# Schematic_diagram.net
KiCad netlist of a schematic drawn in Altium Designer
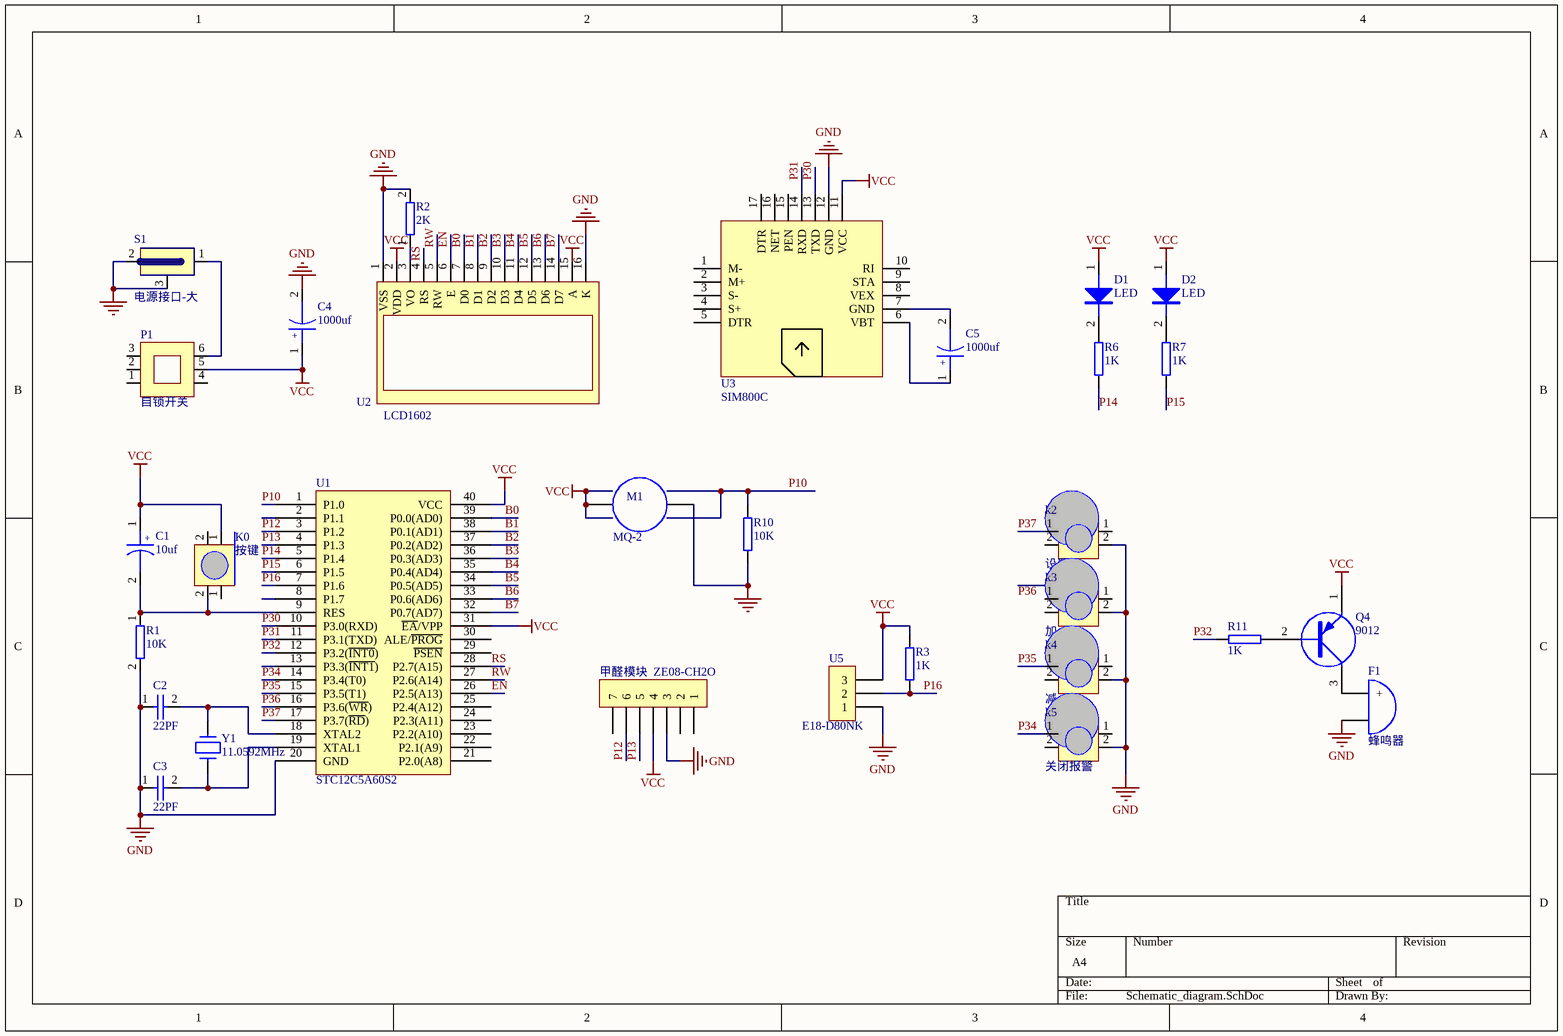
[diagram p0: Schematic_diagram.SchDoc]

(export (version "E")
  (design (tool "Eeschema 10.0.6"))
  (components
    (comp (ref "C1") (value "10uf") (footprint "电容-电解10UF") (libsource (lib "元件集成库") (part "电解电容")))
    (comp (ref "C2") (value "22PF") (footprint "电容-瓷片") (libsource (lib "元件集成库") (part "瓷片电容")))
    (comp (ref "C3") (value "22PF") (footprint "电容-瓷片") (libsource (lib "元件集成库") (part "瓷片电容")))
    (comp (ref "C4")
      (value "1000uf")
      (footprint "电容-电解1000UF - 25V")
      (libsource (lib "元件集成库") (part "电解电容-1000uf-25v"))
    )
    (comp (ref "C5")
      (value "1000uf")
      (footprint "电容-电解1000UF - 25V")
      (libsource (lib "元件集成库") (part "电解电容-1000uf-25v"))
    )
    (comp (ref "D1") (value "LED") (footprint "LED-5MM") (libsource (lib "元件集成库") (part "LED-5MM")))
    (comp (ref "D2") (value "LED") (footprint "LED-5MM") (libsource (lib "元件集成库") (part "LED-5MM")))
    (comp (ref "F1") (value "蜂鸣器") (footprint "蜂鸣器") (libsource (lib "taobao") (part "蜂鸣器")))
    (comp (ref "K0") (value "按键") (footprint "按键") (libsource (lib "") (part "按键_1")))
    (comp (ref "k2") (value "设置") (footprint "按键") (libsource (lib "元件集成库") (part "按键")))
    (comp (ref "k3") (value "加") (footprint "按键") (libsource (lib "元件集成库") (part "按键")))
    (comp (ref "k4") (value "减") (footprint "按键") (libsource (lib "元件集成库") (part "按键")))
    (comp (ref "k5") (value "关闭报警") (footprint "按键") (libsource (lib "元件集成库") (part "按键")))
    (comp (ref "M1") (value "MQ-2") (libsource (lib "*") (part "METER")))
    (comp (ref "P1") (value "自锁开关") (footprint "自锁开关") (libsource (lib "元件集成库") (part "自锁开关")))
    (comp (ref "Q4") (value "9012") (footprint "三极管") (libsource (lib "元件集成库") (part "PNP三极管")))
    (comp (ref "R1") (value "10K") (footprint "电阻") (libsource (lib "") (part "电阻-定值_1")))
    (comp (ref "R2") (value "2K") (footprint "电阻") (libsource (lib "") (part "电阻-定值_1")))
    (comp (ref "R3") (value "1K") (footprint "电阻") (libsource (lib "元件集成库") (part "电阻-定值")))
    (comp (ref "R6") (value "1K") (footprint "电阻") (libsource (lib "元件集成库") (part "电阻-定值")))
    (comp (ref "R7") (value "1K") (footprint "电阻") (libsource (lib "元件集成库") (part "电阻-定值")))
    (comp (ref "R10") (value "10K") (footprint "电阻") (libsource (lib "元件集成库") (part "电阻-定值")))
    (comp (ref "R11") (value "1K") (footprint "电阻") (libsource (lib "元件集成库") (part "电阻-定值")))
    (comp (ref "S1") (value "电源接口-大") (footprint "电源座-大") (libsource (lib "元件集成库") (part "电源接口-大")))
    (comp (ref "U1") (value "STC12C5A60S2") (footprint "底座40P") (libsource (lib "元件集成库") (part "STC89C52")))
    (comp (ref "U2") (value "LCD1602") (footprint "LCD1602") (libsource (lib "元件集成库") (part "LCD1602")))
    (comp (ref "U3") (value "SIM800C") (footprint "SIM800C") (libsource (lib "元件集成库") (part "SIM800C")))
    (comp (ref "U5") (value "E18-D80NK") (footprint "排针3P") (libsource (lib "taobao") (part "端子3P")))
    (comp (ref "Y1") (value "11.0592MHz") (footprint "晶振") (libsource (lib "元件集成库") (part "晶振")))
    (comp (ref "甲醛模块") (value "ZE08-CH2O") (footprint "排针7P") (libsource (lib "taobao") (part "端子7P")))
  )
  (nets
    (net (code "1") (name "/B0") (class "Default")
      (node (ref "U1") (pin "39") (pinfunction "P0.0(AD0)_39") (pintype "passive"))
      (node (ref "U2") (pin "7") (pinfunction "D0_7") (pintype "passive"))
    )
    (net (code "2") (name "/B1") (class "Default")
      (node (ref "U1") (pin "38") (pinfunction "P0.1(AD1)_38") (pintype "passive"))
      (node (ref "U2") (pin "8") (pinfunction "D1_8") (pintype "passive"))
    )
    (net (code "3") (name "/B2") (class "Default")
      (node (ref "U1") (pin "37") (pinfunction "P0.2(AD2)_37") (pintype "passive"))
      (node (ref "U2") (pin "9") (pinfunction "D2_9") (pintype "passive"))
    )
    (net (code "4") (name "/B3") (class "Default")
      (node (ref "U1") (pin "36") (pinfunction "P0.3(AD3)_36") (pintype "passive"))
      (node (ref "U2") (pin "10") (pinfunction "D3_10") (pintype "passive"))
    )
    (net (code "5") (name "/B4") (class "Default")
      (node (ref "U1") (pin "35") (pinfunction "P0.4(AD4)_35") (pintype "passive"))
      (node (ref "U2") (pin "11") (pinfunction "D4_11") (pintype "passive"))
    )
    (net (code "6") (name "/B5") (class "Default")
      (node (ref "U1") (pin "34") (pinfunction "P0.5(AD5)_34") (pintype "passive"))
      (node (ref "U2") (pin "12") (pinfunction "D5_12") (pintype "passive"))
    )
    (net (code "7") (name "/B6") (class "Default")
      (node (ref "U1") (pin "33") (pinfunction "P0.6(AD6)_33") (pintype "passive"))
      (node (ref "U2") (pin "13") (pinfunction "D6_13") (pintype "passive"))
    )
    (net (code "8") (name "/B7") (class "Default")
      (node (ref "U1") (pin "32") (pinfunction "P0.7(AD7)_32") (pintype "passive"))
      (node (ref "U2") (pin "14") (pinfunction "D7_14") (pintype "passive"))
    )
    (net (code "9") (name "/EN") (class "Default")
      (node (ref "U1") (pin "26") (pinfunction "P2.5(A13)_26") (pintype "passive"))
      (node (ref "U2") (pin "6") (pinfunction "E_6") (pintype "passive"))
    )
    (net (code "10") (name "/P10") (class "Default")
      (node (ref "R10") (pin "2") (pinfunction "2_2") (pintype "passive"))
      (node (ref "U1") (pin "1") (pinfunction "P1.0_1") (pintype "passive"))
    )
    (net (code "11") (name "/P12") (class "Default")
      (node (ref "U1") (pin "3") (pinfunction "P1.2_3") (pintype "passive"))
      (node (ref "甲醛模块") (pin "2") (pinfunction "6_2") (pintype "passive"))
    )
    (net (code "12") (name "/P13") (class "Default")
      (node (ref "U1") (pin "4") (pinfunction "P1.3_4") (pintype "passive"))
      (node (ref "甲醛模块") (pin "3") (pinfunction "5_3") (pintype "passive"))
    )
    (net (code "13") (name "/P14") (class "Default")
      (node (ref "R6") (pin "1") (pinfunction "1_1") (pintype "passive"))
      (node (ref "U1") (pin "5") (pinfunction "P1.4_5") (pintype "passive"))
    )
    (net (code "14") (name "/P15") (class "Default")
      (node (ref "R7") (pin "1") (pinfunction "1_1") (pintype "passive"))
      (node (ref "U1") (pin "6") (pinfunction "P1.5_6") (pintype "passive"))
    )
    (net (code "15") (name "/P16") (class "Default")
      (node (ref "R3") (pin "1") (pinfunction "1_1") (pintype "passive"))
      (node (ref "U1") (pin "7") (pinfunction "P1.6_7") (pintype "passive"))
      (node (ref "U5") (pin "2") (pinfunction "2_2") (pintype "passive"))
    )
    (net (code "16") (name "/P30") (class "Default")
      (node (ref "U1") (pin "10") (pinfunction "P3.0(RXD)_10") (pintype "passive"))
      (node (ref "U3") (pin "13") (pinfunction "TXD_13") (pintype "passive"))
    )
    (net (code "17") (name "/P31") (class "Default")
      (node (ref "U1") (pin "11") (pinfunction "P3.1(TXD)_11") (pintype "passive"))
      (node (ref "U3") (pin "14") (pinfunction "RXD_14") (pintype "passive"))
    )
    (net (code "18") (name "/P32") (class "Default")
      (node (ref "R11") (pin "1") (pinfunction "1_1") (pintype "passive"))
      (node (ref "U1") (pin "12") (pinfunction "P3.2(~{INT0})_12") (pintype "passive"))
    )
    (net (code "19") (name "/P34") (class "Default")
      (node (ref "U1") (pin "14") (pinfunction "P3.4(T0)_14") (pintype "passive"))
      (node (ref "k5") (pin "1") (pinfunction "1_1") (pintype "passive"))
    )
    (net (code "20") (name "/P35") (class "Default")
      (node (ref "U1") (pin "15") (pinfunction "P3.5(T1)_15") (pintype "passive"))
      (node (ref "k4") (pin "1") (pinfunction "1_1") (pintype "passive"))
    )
    (net (code "21") (name "/P36") (class "Default")
      (node (ref "U1") (pin "16") (pinfunction "P3.6(~{WR})_16") (pintype "passive"))
    )
    (net (code "22") (name "/P37") (class "Default")
      (node (ref "U1") (pin "17") (pinfunction "P3.7(~{RD})_17") (pintype "passive"))
      (node (ref "k2") (pin "1") (pinfunction "1_1") (pintype "passive"))
    )
    (net (code "23") (name "/RS") (class "Default")
      (node (ref "U1") (pin "28") (pinfunction "P2.7(A15)_28") (pintype "passive"))
      (node (ref "U2") (pin "4") (pinfunction "RS_4") (pintype "passive"))
    )
    (net (code "24") (name "/RW") (class "Default")
      (node (ref "U1") (pin "27") (pinfunction "P2.6(A14)_27") (pintype "passive"))
      (node (ref "U2") (pin "5") (pinfunction "RW_5") (pintype "passive"))
    )
    (net (code "25") (name "GND") (class "Default")
      (node (ref "C2") (pin "1") (pinfunction "1_1") (pintype "passive"))
      (node (ref "C3") (pin "1") (pinfunction "1_1") (pintype "passive"))
      (node (ref "C4") (pin "2") (pinfunction "2_2") (pintype "passive"))
      (node (ref "F1") (pin "2") (pinfunction "B_2") (pintype "passive"))
      (node (ref "M1") (pin "2") (pinfunction "2_2") (pintype "passive"))
      (node (ref "R1") (pin "2") (pinfunction "2_2") (pintype "passive"))
      (node (ref "R10") (pin "1") (pinfunction "1_1") (pintype "passive"))
      (node (ref "R2") (pin "2") (pinfunction "2_2") (pintype "passive"))
      (node (ref "S1") (pin "2") (pinfunction "2_2") (pintype "passive"))
      (node (ref "S1") (pin "3") (pinfunction "3_3") (pintype "passive"))
      (node (ref "U1") (pin "20") (pinfunction "GND_20") (pintype "passive"))
      (node (ref "U2") (pin "1") (pinfunction "VSS_1") (pintype "passive"))
      (node (ref "U2") (pin "16") (pinfunction "K_16") (pintype "passive"))
      (node (ref "U3") (pin "12") (pinfunction "GND_12") (pintype "passive"))
      (node (ref "U5") (pin "1") (pinfunction "1_1") (pintype "passive"))
      (node (ref "k2") (pin "2") (pinfunction "2_2") (pintype "passive"))
      (node (ref "k3") (pin "2") (pinfunction "2_2") (pintype "passive"))
      (node (ref "k4") (pin "2") (pinfunction "2_2") (pintype "passive"))
      (node (ref "k5") (pin "2") (pinfunction "2_2") (pintype "passive"))
      (node (ref "甲醛模块") (pin "5") (pinfunction "3_5") (pintype "passive"))
    )
    (net (code "26") (name "Net-(C5-Pad2)") (class "Default")
      (node (ref "C5") (pin "2") (pinfunction "2_2") (pintype "passive"))
      (node (ref "U3") (pin "7") (pinfunction "GND_7") (pintype "passive"))
    )
    (net (code "27") (name "Net-(D1-Pad2)") (class "Default")
      (node (ref "D1") (pin "2") (pinfunction "2_2") (pintype "passive"))
      (node (ref "R6") (pin "2") (pinfunction "2_2") (pintype "passive"))
    )
    (net (code "28") (name "Net-(D2-Pad2)") (class "Default")
      (node (ref "D2") (pin "2") (pinfunction "2_2") (pintype "passive"))
      (node (ref "R7") (pin "2") (pinfunction "2_2") (pintype "passive"))
    )
    (net (code "29") (name "Net-(F1-+)") (class "Default")
      (node (ref "F1") (pin "1") (pinfunction "+_1") (pintype "passive"))
      (node (ref "Q4") (pin "3") (pinfunction "C_3") (pintype "passive"))
    )
    (net (code "30") (name "Net-(P1-Pad6)") (class "Default")
      (node (ref "P1") (pin "6") (pinfunction "6_6") (pintype "passive"))
      (node (ref "S1") (pin "1") (pinfunction "1_1") (pintype "passive"))
    )
    (net (code "31") (name "Net-(Q4-B)") (class "Default")
      (node (ref "Q4") (pin "2") (pinfunction "B_2") (pintype "passive"))
      (node (ref "R11") (pin "2") (pinfunction "2_2") (pintype "passive"))
    )
    (net (code "32") (name "Net-(U1-RES)") (class "Default")
      (node (ref "C1") (pin "2") (pinfunction "2_2") (pintype "passive"))
      (node (ref "K0") (pin "2") (pinfunction "2_2") (pintype "passive"))
      (node (ref "R1") (pin "1") (pinfunction "1_1") (pintype "passive"))
      (node (ref "U1") (pin "9") (pinfunction "RES_9") (pintype "passive"))
    )
    (net (code "33") (name "Net-(U1-XTAL1)") (class "Default")
      (node (ref "C3") (pin "2") (pinfunction "2_2") (pintype "passive"))
      (node (ref "U1") (pin "19") (pinfunction "XTAL1_19") (pintype "passive"))
      (node (ref "Y1") (pin "2") (pinfunction "2_2") (pintype "passive"))
    )
    (net (code "34") (name "Net-(U1-XTAL2)") (class "Default")
      (node (ref "C2") (pin "2") (pinfunction "2_2") (pintype "passive"))
      (node (ref "U1") (pin "18") (pinfunction "XTAL2_18") (pintype "passive"))
      (node (ref "Y1") (pin "1") (pinfunction "1_1") (pintype "passive"))
    )
    (net (code "35") (name "Net-(U2-VO)") (class "Default")
      (node (ref "R2") (pin "1") (pinfunction "1_1") (pintype "passive"))
      (node (ref "U2") (pin "3") (pinfunction "VO_3") (pintype "passive"))
    )
    (net (code "36") (name "Net-(U3-VBT)") (class "Default")
      (node (ref "C5") (pin "1") (pinfunction "1_1") (pintype "passive"))
      (node (ref "U3") (pin "6") (pinfunction "VBT_6") (pintype "passive"))
    )
    (net (code "37") (name "VCC") (class "Default")
      (node (ref "C1") (pin "1") (pinfunction "1_1") (pintype "passive"))
      (node (ref "C4") (pin "1") (pinfunction "1_1") (pintype "passive"))
      (node (ref "D1") (pin "1") (pinfunction "1_1") (pintype "passive"))
      (node (ref "D2") (pin "1") (pinfunction "1_1") (pintype "passive"))
      (node (ref "K0") (pin "1") (pinfunction "1_1") (pintype "passive"))
      (node (ref "M1") (pin "1") (pinfunction "1_1") (pintype "passive"))
      (node (ref "P1") (pin "5") (pinfunction "5_5") (pintype "passive"))
      (node (ref "Q4") (pin "1") (pinfunction "E_1") (pintype "passive"))
      (node (ref "R3") (pin "2") (pinfunction "2_2") (pintype "passive"))
      (node (ref "U1") (pin "31") (pinfunction "~{EA}/VPP_31") (pintype "passive"))
      (node (ref "U1") (pin "40") (pinfunction "VCC_40") (pintype "passive"))
      (node (ref "U2") (pin "15") (pinfunction "A_15") (pintype "passive"))
      (node (ref "U2") (pin "2") (pinfunction "VDD_2") (pintype "passive"))
      (node (ref "U3") (pin "11") (pinfunction "VCC_11") (pintype "passive"))
      (node (ref "U5") (pin "3") (pinfunction "3_3") (pintype "passive"))
      (node (ref "甲醛模块") (pin "4") (pinfunction "4_4") (pintype "passive"))
    )
    (net (code "38") (name "unconnected-(K0-Pad1)") (class "Default")
      (node (ref "K0") (pin "1") (pinfunction "1_1") (pintype "passive"))
    )
    (net (code "39") (name "unconnected-(K0-Pad2)") (class "Default")
      (node (ref "K0") (pin "2") (pinfunction "2_2") (pintype "passive"))
    )
    (net (code "40") (name "unconnected-(P1-Pad1)") (class "Default")
      (node (ref "P1") (pin "1") (pinfunction "1_1") (pintype "passive"))
    )
    (net (code "41") (name "unconnected-(P1-Pad2)") (class "Default")
      (node (ref "P1") (pin "2") (pinfunction "2_2") (pintype "passive"))
    )
    (net (code "42") (name "unconnected-(P1-Pad3)") (class "Default")
      (node (ref "P1") (pin "3") (pinfunction "3_3") (pintype "passive"))
    )
    (net (code "43") (name "unconnected-(P1-Pad4)") (class "Default")
      (node (ref "P1") (pin "4") (pinfunction "4_4") (pintype "passive"))
    )
    (net (code "44") (name "unconnected-(U1-ALE{slash}~{PROG}-Pad30)") (class "Default")
      (node (ref "U1") (pin "30") (pinfunction "ALE/~{PROG}_30") (pintype "passive"))
    )
    (net (code "45") (name "unconnected-(U1-P1.1-Pad2)") (class "Default")
      (node (ref "U1") (pin "2") (pinfunction "P1.1_2") (pintype "passive"))
    )
    (net (code "46") (name "unconnected-(U1-P1.7-Pad8)") (class "Default")
      (node (ref "U1") (pin "8") (pinfunction "P1.7_8") (pintype "passive"))
    )
    (net (code "47") (name "unconnected-(U1-P2.0(A8)-Pad21)") (class "Default")
      (node (ref "U1") (pin "21") (pinfunction "P2.0(A8)_21") (pintype "passive"))
    )
    (net (code "48") (name "unconnected-(U1-P2.1(A9)-Pad22)") (class "Default")
      (node (ref "U1") (pin "22") (pinfunction "P2.1(A9)_22") (pintype "passive"))
    )
    (net (code "49") (name "unconnected-(U1-P2.2(A10)-Pad23)") (class "Default")
      (node (ref "U1") (pin "23") (pinfunction "P2.2(A10)_23") (pintype "passive"))
    )
    (net (code "50") (name "unconnected-(U1-P2.3(A11)-Pad24)") (class "Default")
      (node (ref "U1") (pin "24") (pinfunction "P2.3(A11)_24") (pintype "passive"))
    )
    (net (code "51") (name "unconnected-(U1-P2.4(A12)-Pad25)") (class "Default")
      (node (ref "U1") (pin "25") (pinfunction "P2.4(A12)_25") (pintype "passive"))
    )
    (net (code "52") (name "unconnected-(U1-P3.3(~{INT1})-Pad13)") (class "Default")
      (node (ref "U1") (pin "13") (pinfunction "P3.3(~{INT1})_13") (pintype "passive"))
    )
    (net (code "53") (name "unconnected-(U1-~{PSEN}-Pad29)") (class "Default")
      (node (ref "U1") (pin "29") (pinfunction "~{PSEN}_29") (pintype "passive"))
    )
    (net (code "54") (name "unconnected-(U3-DTR-Pad5)") (class "Default")
      (node (ref "U3") (pin "5") (pinfunction "DTR_5") (pintype "passive"))
    )
    (net (code "55") (name "unconnected-(U3-DTR-Pad17)") (class "Default")
      (node (ref "U3") (pin "17") (pinfunction "DTR_17") (pintype "passive"))
    )
    (net (code "56") (name "unconnected-(U3-M+-Pad2)") (class "Default")
      (node (ref "U3") (pin "2") (pinfunction "M+_2") (pintype "passive"))
    )
    (net (code "57") (name "unconnected-(U3-M--Pad1)") (class "Default")
      (node (ref "U3") (pin "1") (pinfunction "M-_1") (pintype "passive"))
    )
    (net (code "58") (name "unconnected-(U3-NET-Pad16)") (class "Default")
      (node (ref "U3") (pin "16") (pinfunction "NET_16") (pintype "passive"))
    )
    (net (code "59") (name "unconnected-(U3-PEN-Pad15)") (class "Default")
      (node (ref "U3") (pin "15") (pinfunction "PEN_15") (pintype "passive"))
    )
    (net (code "60") (name "unconnected-(U3-RI-Pad10)") (class "Default")
      (node (ref "U3") (pin "10") (pinfunction "RI_10") (pintype "passive"))
    )
    (net (code "61") (name "unconnected-(U3-S+-Pad4)") (class "Default")
      (node (ref "U3") (pin "4") (pinfunction "S+_4") (pintype "passive"))
    )
    (net (code "62") (name "unconnected-(U3-S--Pad3)") (class "Default")
      (node (ref "U3") (pin "3") (pinfunction "S-_3") (pintype "passive"))
    )
    (net (code "63") (name "unconnected-(U3-STA-Pad9)") (class "Default")
      (node (ref "U3") (pin "9") (pinfunction "STA_9") (pintype "passive"))
    )
    (net (code "64") (name "unconnected-(U3-VEX-Pad8)") (class "Default")
      (node (ref "U3") (pin "8") (pinfunction "VEX_8") (pintype "passive"))
    )
    (net (code "65") (name "unconnected-(k2-Pad1)") (class "Default")
      (node (ref "k2") (pin "1") (pinfunction "1_1") (pintype "passive"))
    )
    (net (code "66") (name "unconnected-(k2-Pad2)") (class "Default")
      (node (ref "k2") (pin "2") (pinfunction "2_2") (pintype "passive"))
    )
    (net (code "67") (name "unconnected-(k3-Pad1)") (class "Default")
      (node (ref "k3") (pin "1") (pinfunction "1_1") (pintype "passive"))
    )
    (net (code "68") (name "unconnected-(k3-Pad1)_1") (class "Default")
      (node (ref "k3") (pin "1") (pinfunction "1_1") (pintype "passive"))
    )
    (net (code "69") (name "unconnected-(k3-Pad2)") (class "Default")
      (node (ref "k3") (pin "2") (pinfunction "2_2") (pintype "passive"))
    )
    (net (code "70") (name "unconnected-(k4-Pad1)") (class "Default")
      (node (ref "k4") (pin "1") (pinfunction "1_1") (pintype "passive"))
    )
    (net (code "71") (name "unconnected-(k4-Pad2)") (class "Default")
      (node (ref "k4") (pin "2") (pinfunction "2_2") (pintype "passive"))
    )
    (net (code "72") (name "unconnected-(k5-Pad1)") (class "Default")
      (node (ref "k5") (pin "1") (pinfunction "1_1") (pintype "passive"))
    )
    (net (code "73") (name "unconnected-(k5-Pad2)") (class "Default")
      (node (ref "k5") (pin "2") (pinfunction "2_2") (pintype "passive"))
    )
    (net (code "74") (name "unconnected-(甲醛模块-1-Pad7)") (class "Default")
      (node (ref "甲醛模块") (pin "7") (pinfunction "1_7") (pintype "passive"))
    )
    (net (code "75") (name "unconnected-(甲醛模块-2-Pad6)") (class "Default")
      (node (ref "甲醛模块") (pin "6") (pinfunction "2_6") (pintype "passive"))
    )
    (net (code "76") (name "unconnected-(甲醛模块-7-Pad1)") (class "Default")
      (node (ref "甲醛模块") (pin "1") (pinfunction "7_1") (pintype "passive"))
    )
  )
)
